# Shield_Schematic_v3.net
KiCad netlist of a schematic drawn in Altium Designer
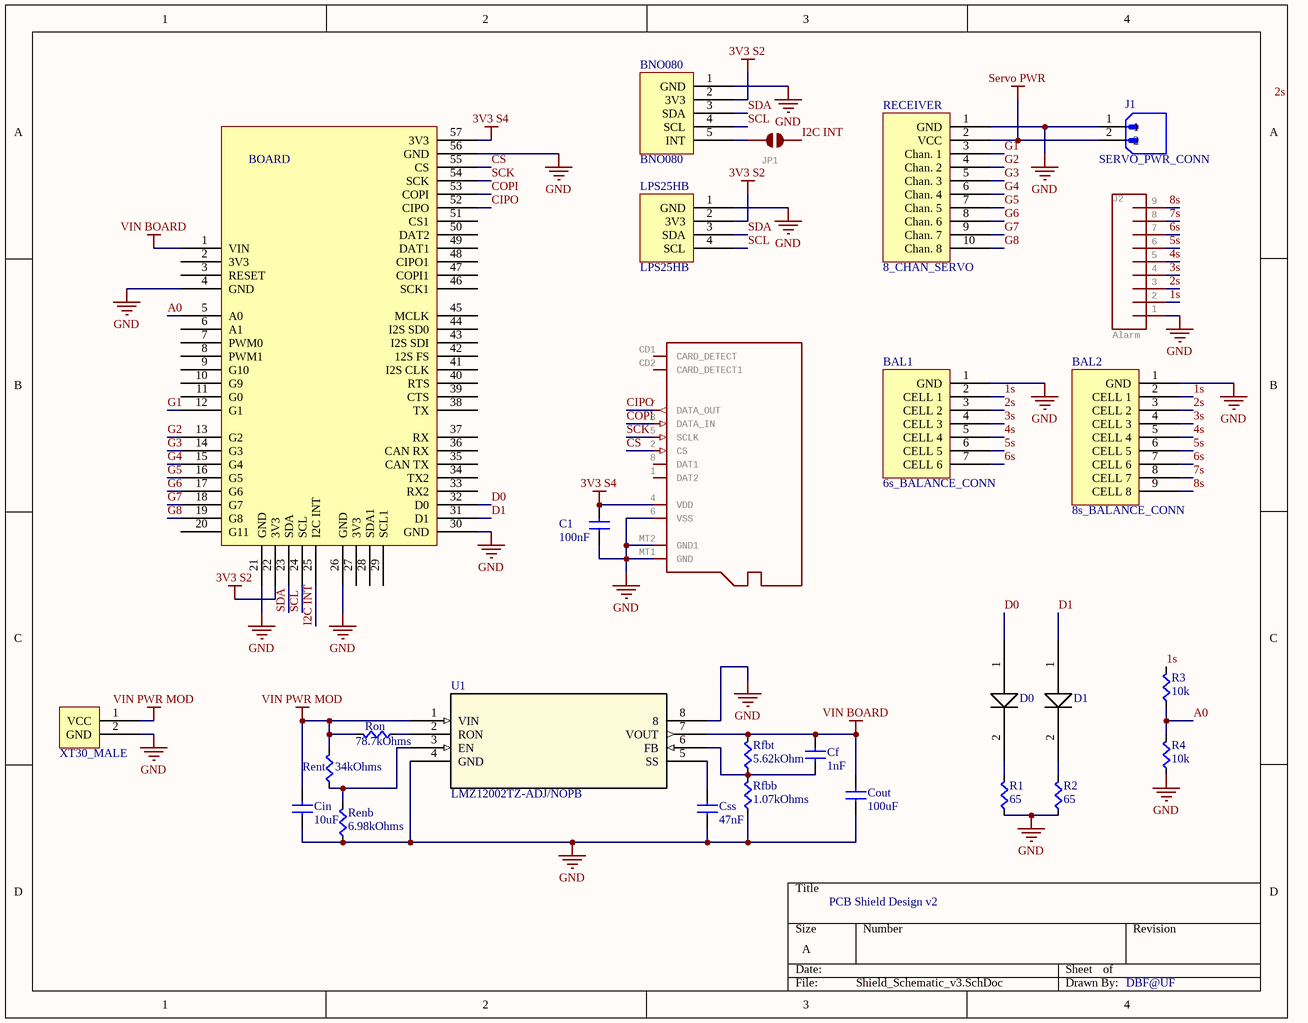
[diagram p0: Shield_Schematic_v3.SchDoc]

(export (version "E")
  (design (tool "Eeschema 10.0.6"))
  (components
    (comp (ref "BAL1")
      (value "6s_BALANCE_CONN")
      (footprint "B7B-XH-A")
      (libsource (lib "DBF") (part "6s_BALANCE_CONN"))
    )
    (comp (ref "BAL2")
      (value "8s_BALANCE_CONN")
      (footprint "B9B-XH-A")
      (libsource (lib "DBF") (part "8s_BALANCE_CONN"))
    )
    (comp (ref "BNO080")
      (value "BNO080")
      (footprint "BNO080")
      (description "BNO080 Breakout Board")
      (libsource (lib "DBF") (part "BNO080"))
    )
    (comp (ref "BOARD") (value "SHIELD") (footprint "Shield") (libsource (lib "DBF") (part "SHIELD")))
    (comp (ref "C1")
      (value "100nF")
      (footprint "CAPC 0603")
      (fields (field (name "Comment") "Cap (0603)"))
      (libsource (lib "DBF") (part "Cap (0603)"))
    )
    (comp (ref "Cf")
      (value "1nF")
      (footprint "CAPC 0402")
      (fields (field (name "Comment") "Cap (0402)"))
      (libsource (lib "DBF") (part "Cap (0402)"))
    )
    (comp (ref "Cin")
      (value "10uF")
      (footprint "CAPC 0805")
      (fields (field (name "Comment") "Cap (0805)"))
      (libsource (lib "DBF") (part "Cap (0805)"))
    )
    (comp (ref "Cout")
      (value "100uF")
      (footprint "CAPC 1206")
      (fields (field (name "Comment") "Cap (1206)"))
      (libsource (lib "DBF") (part "Cap (1206)"))
    )
    (comp (ref "Css")
      (value "47nF")
      (footprint "CAPC 0805")
      (fields (field (name "Comment") "Cap (0805)"))
      (libsource (lib "DBF") (part "Cap (0805)"))
    )
    (comp (ref "D0") (value "LED (0805)") (footprint "LED 0805") (libsource (lib "DBF") (part "LED (0805)")))
    (comp (ref "D1") (value "LED (0805)") (footprint "LED 0805") (libsource (lib "DBF") (part "LED (0805)")))
    (comp (ref "J1")
      (value "SERVO_PWR_CONN")
      (footprint "1053091102")
      (description "Connector Header Through Hole 2 position 0.098 (2.50mm)")
      (fields (field (name "MF") "Molex") (field (name "MP") "1053091102"))
      (libsource (lib "DBF") (part "SERVO_PWR_CONN"))
    )
    (comp (ref "J2")
      (value "Alarm")
      (footprint "1X09_NO_SILK")
      (libsource (lib "DBF") (part "CONN_09NO_SILK_FEMALE_PTH"))
    )
    (comp (ref "JP1")
      (value "Normally open jumper    This jumper has two pads in close proximity to each other. Apply solder to close the connection.   Round pads are easier to solder for beginners, but are a lot larger.   SparkFun Product that uses the round pads:  SparkFun EL Sequencer")
      (footprint "SMT-JUMPER_2_NO_SILK")
      (libsource (lib "DBF") (part "JUMPER-SMT_2_NO_SILK"))
    )
    (comp (ref "LPS25HB")
      (value "LPS25HB")
      (footprint "LPS25HB")
      (description "LPS25HB Breakout Board")
      (libsource (lib "DBF") (part "LPS25HB"))
    )
    (comp (ref "R1")
      (value "65")
      (footprint "RES 0603")
      (fields (field (name "Comment") "Res (0603)"))
      (libsource (lib "DBF") (part "Res (0603)"))
    )
    (comp (ref "R2")
      (value "65")
      (footprint "RES 0603")
      (fields (field (name "Comment") "Res (0603)"))
      (libsource (lib "DBF") (part "Res (0603)"))
    )
    (comp (ref "R3")
      (value "10k")
      (footprint "RES 0603")
      (fields (field (name "Comment") "Res (0603)"))
      (libsource (lib "DBF") (part "Res (0603)"))
    )
    (comp (ref "R4")
      (value "10k")
      (footprint "RES 0603")
      (fields (field (name "Comment") "Res (0603)"))
      (libsource (lib "DBF") (part "Res (0603)"))
    )
    (comp (ref "RECEIVER")
      (value "8_CHAN_SERVO")
      (footprint "8_CHAN_SERVO")
      (libsource (lib "DBF") (part "8_CHAN_SERVO"))
    )
    (comp (ref "Renb")
      (value "6.98kOhms")
      (footprint "RES 0805")
      (fields (field (name "Comment") "Res (0805)"))
      (libsource (lib "DBF") (part "Res (0805)"))
    )
    (comp (ref "Rent")
      (value "34kOhms")
      (footprint "RES 0805")
      (fields (field (name "Comment") "Res (0805)"))
      (libsource (lib "DBF") (part "Res (0805)"))
    )
    (comp (ref "Rfbb")
      (value "1.07kOhms")
      (footprint "RES 0805")
      (fields (field (name "Comment") "Res (0805)"))
      (libsource (lib "DBF") (part "Res (0805)"))
    )
    (comp (ref "Rfbt")
      (value "5.62kOhm")
      (footprint "RES 0805")
      (fields (field (name "Comment") "Res (0805)"))
      (libsource (lib "DBF") (part "Res (0805)"))
    )
    (comp (ref "Ron")
      (value "78.7kOhms")
      (footprint "RES 0805")
      (fields (field (name "Comment") "Res (0805)"))
      (libsource (lib "DBF") (part "Res (0805)"))
    )
    (comp (ref "U1")
      (value "LMZ12002TZ-ADJ/NOPB")
      (footprint "LMZ12002")
      (description "2A SIMPLE SWITCHER® Power Module with 20V Maximum Input Voltage")
      (fields
        (field (name "MANUFACTURER") "Texas Instruments")
        (field (name "COPYRIGHT") "Copyright (C) 2018 Accelerated Designs. All rights reserved")
      )
      (libsource (lib "DBF") (part "LMZ12002TZ-ADJ/NOPB"))
    )
    (comp (ref "uSD")
      (value "Micro-SD / Transflash card holder with SPI pinout   For the 3M # 2908-05WB-MG and/or 4UCON #19656 push-push type")
      (footprint "MICROSD")
      (libsource (lib "DBF") (part "MICROSD"))
    )
    (comp (ref "XT30") (value "XT30_MALE") (footprint "XT30_MALE") (libsource (lib "DBF") (part "XT30_MALE")))
  )
  (nets
    (net (code "1") (name "/1s") (class "Default")
      (node (ref "BAL1") (pin "2") (pinfunction "CELL_1_2") (pintype "passive"))
      (node (ref "BAL2") (pin "2") (pinfunction "CELL_1_2") (pintype "passive"))
      (node (ref "J2") (pin "2") (pinfunction "2_2") (pintype "passive"))
      (node (ref "R3") (pin "1") (pinfunction "A_1") (pintype "passive"))
    )
    (net (code "2") (name "/2s") (class "Default")
      (node (ref "BAL1") (pin "3") (pinfunction "CELL_2_3") (pintype "passive"))
      (node (ref "BAL2") (pin "3") (pinfunction "CELL_2_3") (pintype "passive"))
      (node (ref "J2") (pin "3") (pinfunction "3_3") (pintype "passive"))
    )
    (net (code "3") (name "/3s") (class "Default")
      (node (ref "BAL1") (pin "4") (pinfunction "CELL_3_4") (pintype "passive"))
      (node (ref "BAL2") (pin "4") (pinfunction "CELL_3_4") (pintype "passive"))
      (node (ref "J2") (pin "4") (pinfunction "4_4") (pintype "passive"))
    )
    (net (code "4") (name "/4s") (class "Default")
      (node (ref "BAL1") (pin "5") (pinfunction "CELL_4_5") (pintype "passive"))
      (node (ref "BAL2") (pin "5") (pinfunction "CELL_4_5") (pintype "passive"))
      (node (ref "J2") (pin "5") (pinfunction "5_5") (pintype "passive"))
    )
    (net (code "5") (name "/5s") (class "Default")
      (node (ref "BAL1") (pin "6") (pinfunction "CELL_5_6") (pintype "passive"))
      (node (ref "BAL2") (pin "6") (pinfunction "CELL_5_6") (pintype "passive"))
      (node (ref "J2") (pin "6") (pinfunction "6_6") (pintype "passive"))
    )
    (net (code "6") (name "/6s") (class "Default")
      (node (ref "BAL1") (pin "7") (pinfunction "CELL_6_7") (pintype "passive"))
      (node (ref "BAL2") (pin "7") (pinfunction "CELL_6_7") (pintype "passive"))
      (node (ref "J2") (pin "7") (pinfunction "7_7") (pintype "passive"))
    )
    (net (code "7") (name "/7s") (class "Default")
      (node (ref "BAL2") (pin "8") (pinfunction "CELL_7_8") (pintype "passive"))
      (node (ref "J2") (pin "8") (pinfunction "8_8") (pintype "passive"))
    )
    (net (code "8") (name "/8s") (class "Default")
      (node (ref "BAL2") (pin "9") (pinfunction "CELL_8_9") (pintype "passive"))
      (node (ref "J2") (pin "9") (pinfunction "9_9") (pintype "passive"))
    )
    (net (code "9") (name "/A0") (class "Default")
      (node (ref "BOARD") (pin "5") (pinfunction "A0_5") (pintype "passive"))
      (node (ref "R3") (pin "2") (pinfunction "B_2") (pintype "passive"))
      (node (ref "R4") (pin "1") (pinfunction "A_1") (pintype "passive"))
    )
    (net (code "10") (name "/CIPO") (class "Default")
      (node (ref "BOARD") (pin "52") (pinfunction "CIPO_52") (pintype "passive"))
      (node (ref "uSD") (pin "7") (pinfunction "DATA_OUT_7") (pintype "output"))
    )
    (net (code "11") (name "/COPI") (class "Default")
      (node (ref "BOARD") (pin "53") (pinfunction "COPI_53") (pintype "passive"))
      (node (ref "uSD") (pin "3") (pinfunction "DATA_IN_3") (pintype "input"))
    )
    (net (code "12") (name "/CS") (class "Default")
      (node (ref "BOARD") (pin "55") (pinfunction "CS_55") (pintype "passive"))
      (node (ref "uSD") (pin "2") (pinfunction "CS_2") (pintype "input"))
    )
    (net (code "13") (name "/D0") (class "Default")
      (node (ref "BOARD") (pin "32") (pinfunction "D0_32") (pintype "passive"))
      (node (ref "D0") (pin "1") (pinfunction "+_1") (pintype "passive"))
    )
    (net (code "14") (name "/D1") (class "Default")
      (node (ref "BOARD") (pin "31") (pinfunction "D1_31") (pintype "passive"))
      (node (ref "D1") (pin "1") (pinfunction "+_1") (pintype "passive"))
    )
    (net (code "15") (name "/G1") (class "Default")
      (node (ref "BOARD") (pin "12") (pinfunction "G1_12") (pintype "passive"))
      (node (ref "RECEIVER") (pin "3") (pinfunction "Chan._1_3") (pintype "passive"))
    )
    (net (code "16") (name "/G2") (class "Default")
      (node (ref "BOARD") (pin "13") (pinfunction "G2_13") (pintype "passive"))
      (node (ref "RECEIVER") (pin "4") (pinfunction "Chan._2_4") (pintype "passive"))
    )
    (net (code "17") (name "/G3") (class "Default")
      (node (ref "BOARD") (pin "14") (pinfunction "G3_14") (pintype "passive"))
      (node (ref "RECEIVER") (pin "5") (pinfunction "Chan._3_5") (pintype "passive"))
    )
    (net (code "18") (name "/G4") (class "Default")
      (node (ref "BOARD") (pin "15") (pinfunction "G4_15") (pintype "passive"))
      (node (ref "RECEIVER") (pin "6") (pinfunction "Chan._4_6") (pintype "passive"))
    )
    (net (code "19") (name "/G5") (class "Default")
      (node (ref "BOARD") (pin "16") (pinfunction "G5_16") (pintype "passive"))
      (node (ref "RECEIVER") (pin "7") (pinfunction "Chan._5_7") (pintype "passive"))
    )
    (net (code "20") (name "/G6") (class "Default")
      (node (ref "BOARD") (pin "17") (pinfunction "G6_17") (pintype "passive"))
      (node (ref "RECEIVER") (pin "8") (pinfunction "Chan._6_8") (pintype "passive"))
    )
    (net (code "21") (name "/G7") (class "Default")
      (node (ref "BOARD") (pin "18") (pinfunction "G7_18") (pintype "passive"))
      (node (ref "RECEIVER") (pin "9") (pinfunction "Chan._7_9") (pintype "passive"))
    )
    (net (code "22") (name "/G8") (class "Default")
      (node (ref "BOARD") (pin "19") (pinfunction "G8_19") (pintype "passive"))
      (node (ref "RECEIVER") (pin "10") (pinfunction "Chan._8_10") (pintype "passive"))
    )
    (net (code "23") (name "/I2C INT") (class "Default")
      (node (ref "BOARD") (pin "25") (pinfunction "I2C_INT_25") (pintype "passive"))
      (node (ref "JP1") (pin "2") (pinfunction "2_2") (pintype "passive"))
    )
    (net (code "24") (name "/SCK") (class "Default")
      (node (ref "BOARD") (pin "54") (pinfunction "SCK_54") (pintype "passive"))
      (node (ref "uSD") (pin "5") (pinfunction "SCLK_5") (pintype "input"))
    )
    (net (code "25") (name "/SCL") (class "Default")
      (node (ref "BNO080") (pin "4") (pinfunction "SCL_4") (pintype "passive"))
      (node (ref "BOARD") (pin "24") (pinfunction "SCL_24") (pintype "passive"))
      (node (ref "LPS25HB") (pin "4") (pinfunction "SCL_4") (pintype "passive"))
    )
    (net (code "26") (name "/SDA") (class "Default")
      (node (ref "BNO080") (pin "3") (pinfunction "SDA_3") (pintype "passive"))
      (node (ref "BOARD") (pin "23") (pinfunction "SDA_23") (pintype "passive"))
      (node (ref "LPS25HB") (pin "3") (pinfunction "SDA_3") (pintype "passive"))
    )
    (net (code "27") (name "3V3 S2") (class "Default")
      (node (ref "BNO080") (pin "2") (pinfunction "3V3_2") (pintype "passive"))
      (node (ref "BOARD") (pin "22") (pinfunction "3V3_22") (pintype "passive"))
      (node (ref "LPS25HB") (pin "2") (pinfunction "3V3_2") (pintype "passive"))
    )
    (net (code "28") (name "3V3 S4") (class "Default")
      (node (ref "BOARD") (pin "57") (pinfunction "3V3_57") (pintype "passive"))
      (node (ref "C1") (pin "1") (pinfunction "A_1") (pintype "passive"))
      (node (ref "uSD") (pin "4") (pinfunction "VDD_4") (pintype "power_in"))
    )
    (net (code "29") (name "GND") (class "Default")
      (node (ref "BAL1") (pin "1") (pinfunction "GND_1") (pintype "passive"))
      (node (ref "BAL2") (pin "1") (pinfunction "GND_1") (pintype "passive"))
      (node (ref "BNO080") (pin "1") (pinfunction "GND_1") (pintype "passive"))
      (node (ref "BOARD") (pin "21") (pinfunction "GND_21") (pintype "passive"))
      (node (ref "BOARD") (pin "26") (pinfunction "GND_26") (pintype "passive"))
      (node (ref "BOARD") (pin "30") (pinfunction "GND_30") (pintype "passive"))
      (node (ref "BOARD") (pin "4") (pinfunction "GND_4") (pintype "passive"))
      (node (ref "BOARD") (pin "56") (pinfunction "GND_56") (pintype "passive"))
      (node (ref "C1") (pin "2") (pinfunction "B_2") (pintype "passive"))
      (node (ref "Cin") (pin "2") (pinfunction "B_2") (pintype "passive"))
      (node (ref "Cout") (pin "2") (pinfunction "B_2") (pintype "passive"))
      (node (ref "Css") (pin "2") (pinfunction "B_2") (pintype "passive"))
      (node (ref "J1") (pin "1") (pinfunction "1_1") (pintype "passive"))
      (node (ref "J2") (pin "1") (pinfunction "1_1") (pintype "passive"))
      (node (ref "LPS25HB") (pin "1") (pinfunction "GND_1") (pintype "passive"))
      (node (ref "R1") (pin "2") (pinfunction "B_2") (pintype "passive"))
      (node (ref "R2") (pin "2") (pinfunction "B_2") (pintype "passive"))
      (node (ref "R4") (pin "2") (pinfunction "B_2") (pintype "passive"))
      (node (ref "RECEIVER") (pin "1") (pinfunction "GND_1") (pintype "passive"))
      (node (ref "Renb") (pin "2") (pinfunction "B_2") (pintype "passive"))
      (node (ref "Rfbb") (pin "2") (pinfunction "B_2") (pintype "passive"))
      (node (ref "U1") (pin "4") (pinfunction "GND_4") (pintype "power_in"))
      (node (ref "U1") (pin "8") (pinfunction "8_8") (pintype "passive"))
      (node (ref "XT30") (pin "2") (pinfunction "GND_2") (pintype "passive"))
      (node (ref "uSD") (pin "6") (pinfunction "VSS_6") (pintype "power_in"))
      (node (ref "uSD") (pin "MT1") (pinfunction "GND_MT1") (pintype "power_in"))
      (node (ref "uSD") (pin "MT2") (pinfunction "GND1_MT2") (pintype "power_in"))
    )
    (net (code "30") (name "Net-(BNO080-INT)") (class "Default")
      (node (ref "BNO080") (pin "5") (pinfunction "INT_5") (pintype "passive"))
      (node (ref "JP1") (pin "1") (pinfunction "1_1") (pintype "passive"))
    )
    (net (code "31") (name "Net-(Cf-B)") (class "Default")
      (node (ref "Cf") (pin "2") (pinfunction "B_2") (pintype "passive"))
      (node (ref "Rfbb") (pin "1") (pinfunction "A_1") (pintype "passive"))
      (node (ref "Rfbt") (pin "2") (pinfunction "B_2") (pintype "passive"))
      (node (ref "U1") (pin "6") (pinfunction "FB_6") (pintype "input"))
    )
    (net (code "32") (name "Net-(Css-A)") (class "Default")
      (node (ref "Css") (pin "1") (pinfunction "A_1") (pintype "passive"))
      (node (ref "U1") (pin "5") (pinfunction "SS_5") (pintype "passive"))
    )
    (net (code "33") (name "Net-(D0--)") (class "Default")
      (node (ref "D0") (pin "2") (pinfunction "-_2") (pintype "passive"))
      (node (ref "R1") (pin "1") (pinfunction "A_1") (pintype "passive"))
    )
    (net (code "34") (name "Net-(D1--)") (class "Default")
      (node (ref "D1") (pin "2") (pinfunction "-_2") (pintype "passive"))
      (node (ref "R2") (pin "1") (pinfunction "A_1") (pintype "passive"))
    )
    (net (code "35") (name "Net-(Renb-A)") (class "Default")
      (node (ref "Renb") (pin "1") (pinfunction "A_1") (pintype "passive"))
      (node (ref "Rent") (pin "2") (pinfunction "B_2") (pintype "passive"))
      (node (ref "U1") (pin "3") (pinfunction "EN_3") (pintype "input"))
    )
    (net (code "36") (name "Net-(Ron-B)") (class "Default")
      (node (ref "Ron") (pin "2") (pinfunction "B_2") (pintype "passive"))
      (node (ref "U1") (pin "2") (pinfunction "RON_2") (pintype "passive"))
    )
    (net (code "37") (name "Servo PWR") (class "Default")
      (node (ref "J1") (pin "2") (pinfunction "2_2") (pintype "passive"))
      (node (ref "RECEIVER") (pin "2") (pinfunction "VCC_2") (pintype "passive"))
    )
    (net (code "38") (name "VIN BOARD") (class "Default")
      (node (ref "BOARD") (pin "1") (pinfunction "VIN_1") (pintype "passive"))
      (node (ref "Cf") (pin "1") (pinfunction "A_1") (pintype "passive"))
      (node (ref "Cout") (pin "1") (pinfunction "A_1") (pintype "passive"))
      (node (ref "Rfbt") (pin "1") (pinfunction "A_1") (pintype "passive"))
      (node (ref "U1") (pin "7") (pinfunction "VOUT_7") (pintype "output"))
    )
    (net (code "39") (name "VIN PWR MOD") (class "Default")
      (node (ref "Cin") (pin "1") (pinfunction "A_1") (pintype "passive"))
      (node (ref "Rent") (pin "1") (pinfunction "A_1") (pintype "passive"))
      (node (ref "Ron") (pin "1") (pinfunction "A_1") (pintype "passive"))
      (node (ref "U1") (pin "1") (pinfunction "VIN_1") (pintype "input"))
      (node (ref "XT30") (pin "1") (pinfunction "VCC_1") (pintype "passive"))
    )
    (net (code "40") (name "unconnected-(BOARD-3V3-Pad2)") (class "Default")
      (node (ref "BOARD") (pin "2") (pinfunction "3V3_2") (pintype "passive"))
    )
    (net (code "41") (name "unconnected-(BOARD-3V3-Pad27)") (class "Default")
      (node (ref "BOARD") (pin "27") (pinfunction "3V3_27") (pintype "passive"))
    )
    (net (code "42") (name "unconnected-(BOARD-12S_FS-Pad42)") (class "Default")
      (node (ref "BOARD") (pin "42") (pinfunction "12S_FS_42") (pintype "passive"))
    )
    (net (code "43") (name "unconnected-(BOARD-A1-Pad6)") (class "Default")
      (node (ref "BOARD") (pin "6") (pinfunction "A1_6") (pintype "passive"))
    )
    (net (code "44") (name "unconnected-(BOARD-CAN_RX-Pad36)") (class "Default")
      (node (ref "BOARD") (pin "36") (pinfunction "CAN_RX_36") (pintype "passive"))
    )
    (net (code "45") (name "unconnected-(BOARD-CAN_TX-Pad35)") (class "Default")
      (node (ref "BOARD") (pin "35") (pinfunction "CAN_TX_35") (pintype "passive"))
    )
    (net (code "46") (name "unconnected-(BOARD-CIPO1-Pad48)") (class "Default")
      (node (ref "BOARD") (pin "48") (pinfunction "CIPO1_48") (pintype "passive"))
    )
    (net (code "47") (name "unconnected-(BOARD-COPI1-Pad47)") (class "Default")
      (node (ref "BOARD") (pin "47") (pinfunction "COPI1_47") (pintype "passive"))
    )
    (net (code "48") (name "unconnected-(BOARD-CS1-Pad51)") (class "Default")
      (node (ref "BOARD") (pin "51") (pinfunction "CS1_51") (pintype "passive"))
    )
    (net (code "49") (name "unconnected-(BOARD-CTS-Pad39)") (class "Default")
      (node (ref "BOARD") (pin "39") (pinfunction "CTS_39") (pintype "passive"))
    )
    (net (code "50") (name "unconnected-(BOARD-DAT1-Pad49)") (class "Default")
      (node (ref "BOARD") (pin "49") (pinfunction "DAT1_49") (pintype "passive"))
    )
    (net (code "51") (name "unconnected-(BOARD-DAT2-Pad50)") (class "Default")
      (node (ref "BOARD") (pin "50") (pinfunction "DAT2_50") (pintype "passive"))
    )
    (net (code "52") (name "unconnected-(BOARD-G0-Pad11)") (class "Default")
      (node (ref "BOARD") (pin "11") (pinfunction "G0_11") (pintype "passive"))
    )
    (net (code "53") (name "unconnected-(BOARD-G9-Pad10)") (class "Default")
      (node (ref "BOARD") (pin "10") (pinfunction "G9_10") (pintype "passive"))
    )
    (net (code "54") (name "unconnected-(BOARD-G10-Pad9)") (class "Default")
      (node (ref "BOARD") (pin "9") (pinfunction "G10_9") (pintype "passive"))
    )
    (net (code "55") (name "unconnected-(BOARD-G11-Pad20)") (class "Default")
      (node (ref "BOARD") (pin "20") (pinfunction "G11_20") (pintype "passive"))
    )
    (net (code "56") (name "unconnected-(BOARD-I2S_CLK-Pad41)") (class "Default")
      (node (ref "BOARD") (pin "41") (pinfunction "I2S_CLK_41") (pintype "passive"))
    )
    (net (code "57") (name "unconnected-(BOARD-I2S_SD0-Pad44)") (class "Default")
      (node (ref "BOARD") (pin "44") (pinfunction "I2S_SD0_44") (pintype "passive"))
    )
    (net (code "58") (name "unconnected-(BOARD-I2S_SDI-Pad43)") (class "Default")
      (node (ref "BOARD") (pin "43") (pinfunction "I2S_SDI_43") (pintype "passive"))
    )
    (net (code "59") (name "unconnected-(BOARD-MCLK-Pad45)") (class "Default")
      (node (ref "BOARD") (pin "45") (pinfunction "MCLK_45") (pintype "passive"))
    )
    (net (code "60") (name "unconnected-(BOARD-PWM0-Pad7)") (class "Default")
      (node (ref "BOARD") (pin "7") (pinfunction "PWM0_7") (pintype "passive"))
    )
    (net (code "61") (name "unconnected-(BOARD-PWM1-Pad8)") (class "Default")
      (node (ref "BOARD") (pin "8") (pinfunction "PWM1_8") (pintype "passive"))
    )
    (net (code "62") (name "unconnected-(BOARD-RESET-Pad3)") (class "Default")
      (node (ref "BOARD") (pin "3") (pinfunction "RESET_3") (pintype "passive"))
    )
    (net (code "63") (name "unconnected-(BOARD-RTS-Pad40)") (class "Default")
      (node (ref "BOARD") (pin "40") (pinfunction "RTS_40") (pintype "passive"))
    )
    (net (code "64") (name "unconnected-(BOARD-RX-Pad37)") (class "Default")
      (node (ref "BOARD") (pin "37") (pinfunction "RX_37") (pintype "passive"))
    )
    (net (code "65") (name "unconnected-(BOARD-RX2-Pad33)") (class "Default")
      (node (ref "BOARD") (pin "33") (pinfunction "RX2_33") (pintype "passive"))
    )
    (net (code "66") (name "unconnected-(BOARD-SCK1-Pad46)") (class "Default")
      (node (ref "BOARD") (pin "46") (pinfunction "SCK1_46") (pintype "passive"))
    )
    (net (code "67") (name "unconnected-(BOARD-SCL1-Pad29)") (class "Default")
      (node (ref "BOARD") (pin "29") (pinfunction "SCL1_29") (pintype "passive"))
    )
    (net (code "68") (name "unconnected-(BOARD-SDA1-Pad28)") (class "Default")
      (node (ref "BOARD") (pin "28") (pinfunction "SDA1_28") (pintype "passive"))
    )
    (net (code "69") (name "unconnected-(BOARD-TX-Pad38)") (class "Default")
      (node (ref "BOARD") (pin "38") (pinfunction "TX_38") (pintype "passive"))
    )
    (net (code "70") (name "unconnected-(BOARD-TX2-Pad34)") (class "Default")
      (node (ref "BOARD") (pin "34") (pinfunction "TX2_34") (pintype "passive"))
    )
    (net (code "71") (name "unconnected-(uSD-CARD_DETECT-PadCD1)") (class "Default")
      (node (ref "uSD") (pin "CD1") (pinfunction "CARD_DETECT_CD1") (pintype "passive"))
    )
    (net (code "72") (name "unconnected-(uSD-CARD_DETECT1-PadCD2)") (class "Default")
      (node (ref "uSD") (pin "CD2") (pinfunction "CARD_DETECT1_CD2") (pintype "passive"))
    )
    (net (code "73") (name "unconnected-(uSD-DAT1-Pad8)") (class "Default")
      (node (ref "uSD") (pin "8") (pinfunction "DAT1_8") (pintype "bidirectional"))
    )
    (net (code "74") (name "unconnected-(uSD-DAT2-Pad1)") (class "Default")
      (node (ref "uSD") (pin "1") (pinfunction "DAT2_1") (pintype "bidirectional"))
    )
  )
)
